# ms5839_with_trub.net
KiCad netlist of a schematic drawn in EAGLE
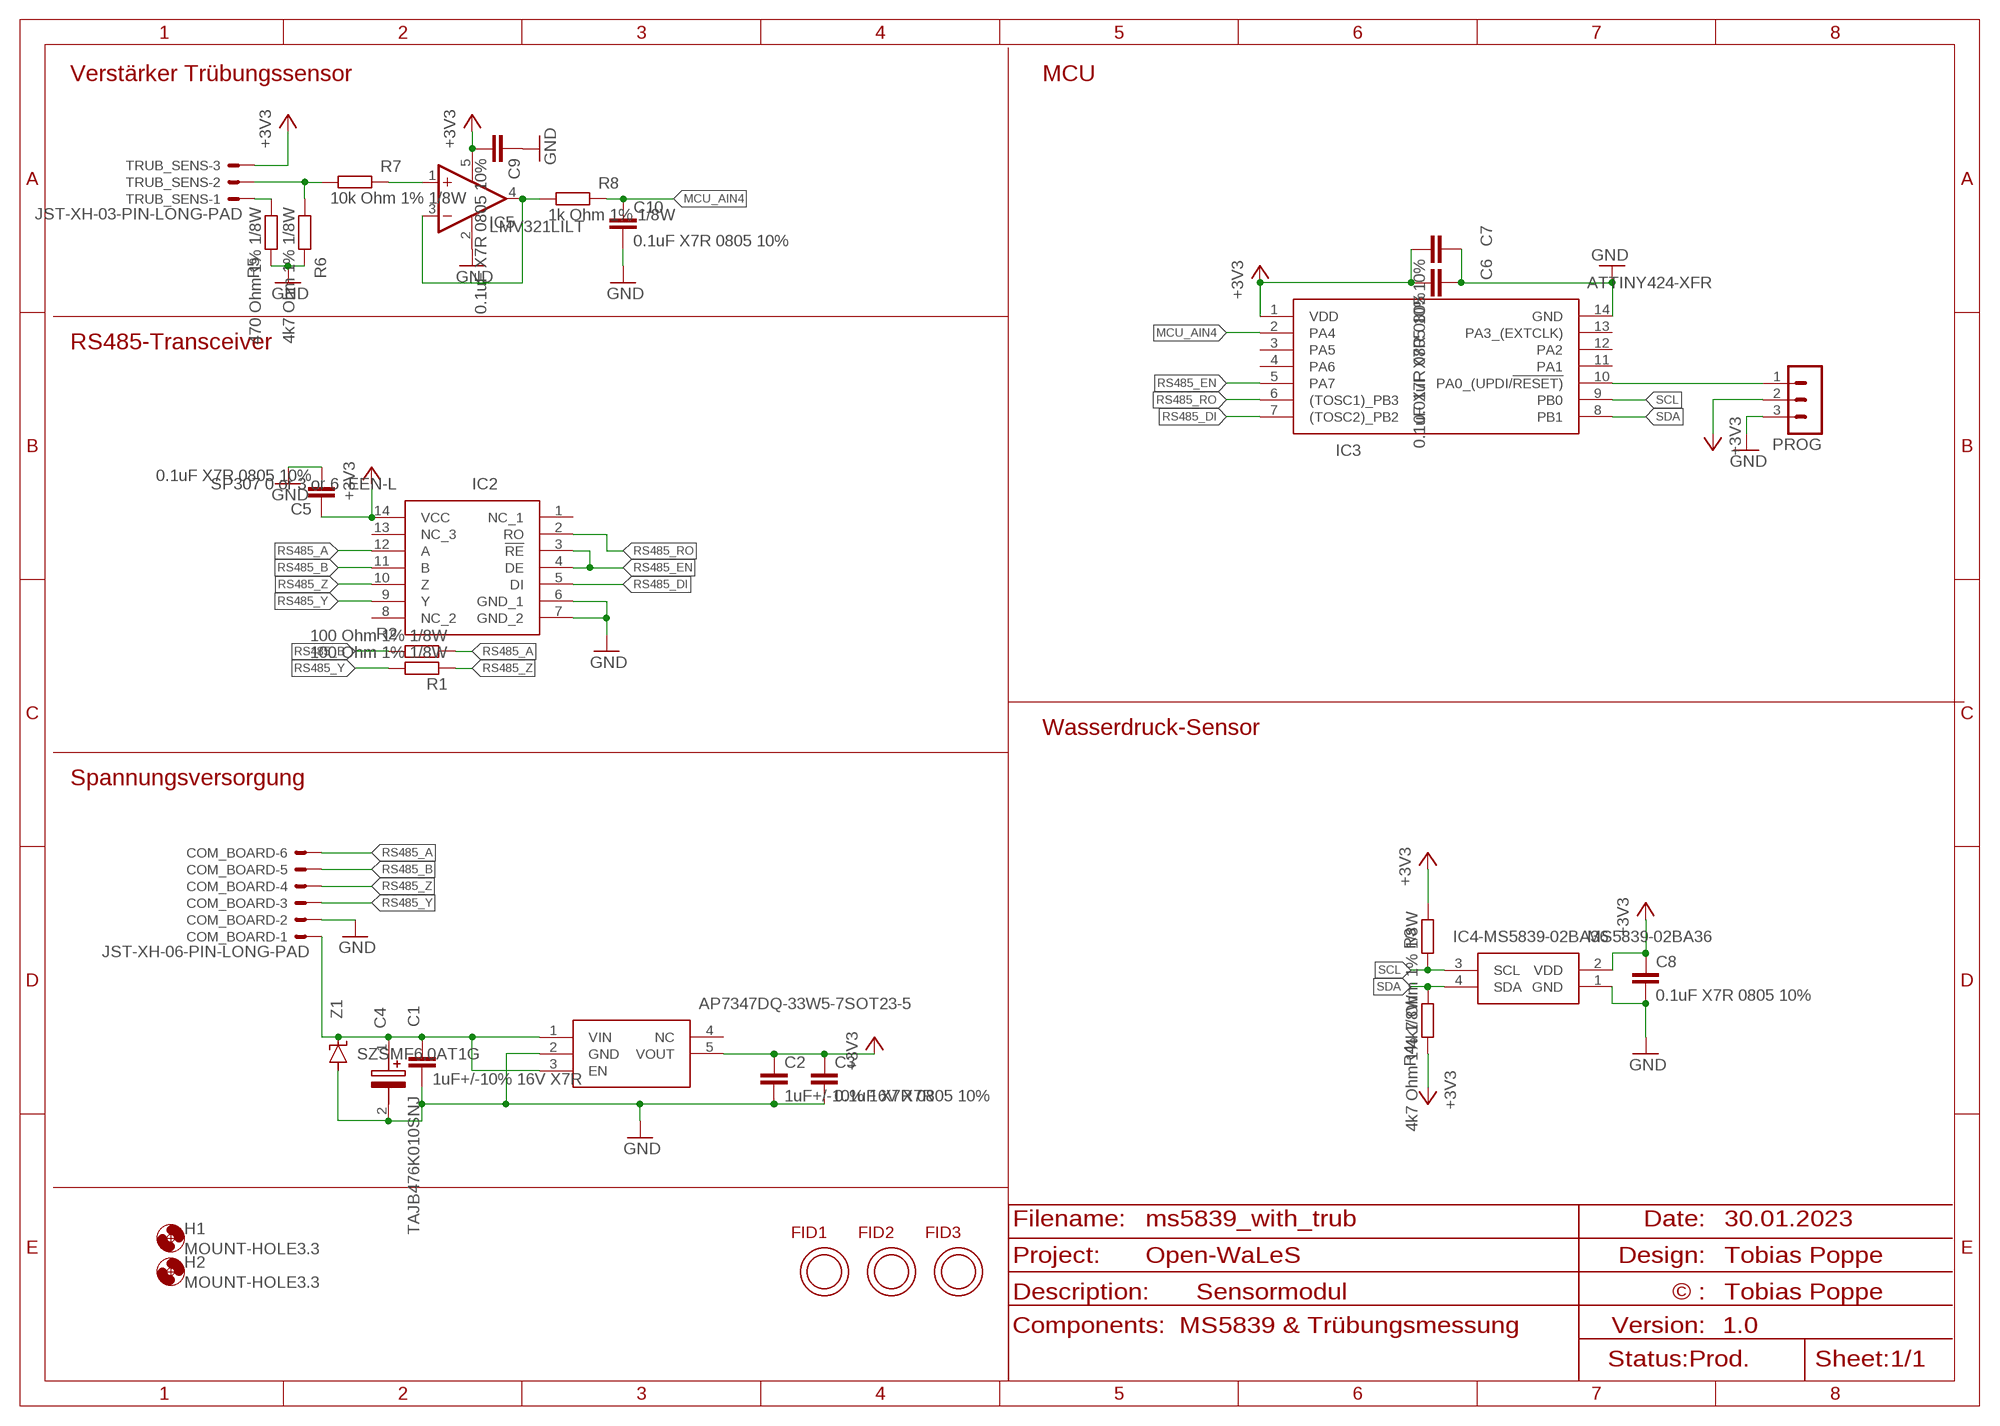
[diagram p0: schematic, sheet 1]

(export (version "E")
  (design (tool "Eeschema 10.0.6"))
  (components
    (comp (ref "C1")
      (value "1uF+/-10% 16V X7R")
      (footprint "eagle-import:C0805")
      (libsource (lib "eagle-import") (part "C-EUC0805"))
    )
    (comp (ref "C2")
      (value "1uF+/-10% 16V X7R")
      (footprint "eagle-import:C0805")
      (libsource (lib "eagle-import") (part "C-EUC0805"))
    )
    (comp (ref "C3")
      (value "0.1uF X7R 0805 10%")
      (footprint "eagle-import:C0805")
      (libsource (lib "eagle-import") (part "C-EUC0805"))
    )
    (comp (ref "C4")
      (value "TAJB476K010SNJ")
      (footprint "eagle-import:CAPPM3528X210N")
      (fields (field (name "MOUSER_PART_NUMBER") "581-TAJB476K010SNJ"))
      (libsource (lib "eagle-import") (part "TAJB476K010SNJ"))
    )
    (comp (ref "C5")
      (value "0.1uF X7R 0805 10%")
      (footprint "eagle-import:C0805")
      (libsource (lib "eagle-import") (part "C-EUC0805"))
    )
    (comp (ref "C6")
      (value "0.1uF X7R 0805 10%")
      (footprint "eagle-import:C0805")
      (libsource (lib "eagle-import") (part "C-EUC0805"))
    )
    (comp (ref "C7")
      (value "0.01uF X7R 0805 10%")
      (footprint "eagle-import:C0805")
      (libsource (lib "eagle-import") (part "C-EUC0805"))
    )
    (comp (ref "C8")
      (value "0.1uF X7R 0805 10%")
      (footprint "eagle-import:C0805")
      (libsource (lib "eagle-import") (part "C-EUC0805"))
    )
    (comp (ref "C9")
      (value "0.1uF X7R 0805 10%")
      (footprint "eagle-import:C0805")
      (libsource (lib "eagle-import") (part "C-EUC0805"))
    )
    (comp (ref "C10")
      (value "0.1uF X7R 0805 10%")
      (footprint "eagle-import:C0805")
      (libsource (lib "eagle-import") (part "C-EUC0805"))
    )
    (comp (ref "COM_BOARD")
      (value "JST-XH-06-PIN-LONG-PAD")
      (footprint "eagle-import:JST-XH-06-PACKAGE-LONG-PAD")
      (libsource (lib "eagle-import") (part "JST-XH-06-PIN-LONG-PAD"))
    )
    (comp (ref "FID1")
      (value "OPEN-PNP-FIDUCIAL")
      (footprint "eagle-import:OPEN-PNP-FIDUCIAL")
      (libsource (lib "eagle-import") (part "OPEN-PNP-FIDUCIAL"))
    )
    (comp (ref "FID2")
      (value "OPEN-PNP-FIDUCIAL")
      (footprint "eagle-import:OPEN-PNP-FIDUCIAL")
      (libsource (lib "eagle-import") (part "OPEN-PNP-FIDUCIAL"))
    )
    (comp (ref "FID3")
      (value "OPEN-PNP-FIDUCIAL")
      (footprint "eagle-import:OPEN-PNP-FIDUCIAL")
      (libsource (lib "eagle-import") (part "OPEN-PNP-FIDUCIAL"))
    )
    (comp (ref "H1")
      (value "MOUNT-HOLE3.3")
      (footprint "eagle-import:3,3")
      (libsource (lib "eagle-import") (part "MOUNT-HOLE3.3"))
    )
    (comp (ref "H2")
      (value "MOUNT-HOLE3.3")
      (footprint "eagle-import:3,3")
      (libsource (lib "eagle-import") (part "MOUNT-HOLE3.3"))
    )
    (comp (ref "IC1")
      (value "AP7347DQ-33W5-7SOT23-5")
      (footprint "eagle-import:SOT95P240X110-5N")
      (libsource (lib "eagle-import") (part "AP7347DQ-33W5-7SOT23-5"))
    )
    (comp (ref "IC2")
      (value "SP307 0 or 3 or 6 EEN-L")
      (footprint "eagle-import:SOIC127P600X175-14N")
      (fields
        (field (name "MANUFACTURER_PART_NUMBER") "SP3076EEN-L")
        (field (name "MOUSER_PART_NUMBER") "701-SP3076EEN-L")
      )
      (libsource (lib "eagle-import") (part "SP3076EEN-L"))
    )
    (comp (ref "IC3")
      (value "ATTINY424-XFR")
      (footprint "eagle-import:SOP65P640X120-14N")
      (fields (field (name "MOUSER_PART_NUMBER") "579-ATTINY424-XFR"))
      (libsource (lib "eagle-import") (part "ATTINY424-XFR"))
    )
    (comp (ref "IC4-MS5839-02BA36")
      (value "MS5839-02BA36")
      (footprint "eagle-import:MS583902BA36")
      (fields (field (name "MOUSER_PART_NUMBER") "824-MS5839-02BA36"))
      (libsource (lib "eagle-import") (part "MS5839-02BA36"))
    )
    (comp (ref "IC5")
      (value "LMV321LILT")
      (footprint "eagle-import:SOT23-5")
      (libsource (lib "eagle-import") (part "LMV321?M5X"))
    )
    (comp (ref "PROG")
      (value "MA03-1")
      (footprint "eagle-import:MA03-1")
      (libsource (lib "eagle-import") (part "MA03-1"))
    )
    (comp (ref "R1")
      (value "100 Ohm 1% 1/8W")
      (footprint "eagle-import:R0805")
      (libsource (lib "eagle-import") (part "R-EU_R0805"))
    )
    (comp (ref "R2")
      (value "100 Ohm 1% 1/8W")
      (footprint "eagle-import:R0805")
      (libsource (lib "eagle-import") (part "R-EU_R0805"))
    )
    (comp (ref "R3")
      (value "4k7 Ohm 1% 1/8W")
      (footprint "eagle-import:R0805")
      (libsource (lib "eagle-import") (part "R-EU_R0805"))
    )
    (comp (ref "R4")
      (value "4k7 Ohm 1% 1/8W")
      (footprint "eagle-import:R0805")
      (libsource (lib "eagle-import") (part "R-EU_R0805"))
    )
    (comp (ref "R5")
      (value "470 Ohm 1% 1/8W")
      (footprint "eagle-import:R0805")
      (libsource (lib "eagle-import") (part "R-EU_R0805"))
    )
    (comp (ref "R6")
      (value "4k7 Ohm 1% 1/8W")
      (footprint "eagle-import:R0805")
      (libsource (lib "eagle-import") (part "R-EU_R0805"))
    )
    (comp (ref "R7")
      (value "10k Ohm 1% 1/8W")
      (footprint "eagle-import:R0805")
      (libsource (lib "eagle-import") (part "R-EU_R0805"))
    )
    (comp (ref "R8")
      (value "1k Ohm 1% 1/8W")
      (footprint "eagle-import:R0805")
      (libsource (lib "eagle-import") (part "R-EU_R0805"))
    )
    (comp (ref "TRUB_SENS")
      (value "JST-XH-03-PIN-LONG-PAD")
      (footprint "eagle-import:JST-XH-03-PACKAGE-LONG-PAD")
      (libsource (lib "eagle-import") (part "JST-XH-03-PIN-LONG-PAD"))
    )
    (comp (ref "Z1")
      (value "SZSMF6.0AT1G")
      (footprint "eagle-import:SOD123")
      (libsource (lib "eagle-import") (part "SZSMF_XX"))
    )
  )
  (nets
    (net (code "1") (name "+3V3") (class "Default")
      (node (ref "C2") (pin "1") (pinfunction "1_1") (pintype "passive"))
      (node (ref "C3") (pin "1") (pinfunction "1_1") (pintype "passive"))
      (node (ref "C5") (pin "1") (pinfunction "1_1") (pintype "passive"))
      (node (ref "C6") (pin "2") (pinfunction "2_2") (pintype "passive"))
      (node (ref "C7") (pin "2") (pinfunction "2_2") (pintype "passive"))
      (node (ref "C8") (pin "1") (pinfunction "1_1") (pintype "passive"))
      (node (ref "C9") (pin "2") (pinfunction "2_2") (pintype "passive"))
      (node (ref "IC1") (pin "5") (pinfunction "VOUT_5") (pintype "bidirectional"))
      (node (ref "IC2") (pin "14") (pinfunction "VCC_14") (pintype "bidirectional"))
      (node (ref "IC3") (pin "1") (pinfunction "VDD_1") (pintype "bidirectional"))
      (node (ref "IC4-MS5839-02BA36") (pin "2") (pinfunction "VDD_2") (pintype "bidirectional"))
      (node (ref "IC5") (pin "5") (pinfunction "V+_5") (pintype "power_in"))
      (node (ref "PROG") (pin "2") (pinfunction "2_2") (pintype "passive"))
      (node (ref "R3") (pin "1") (pinfunction "1_1") (pintype "passive"))
      (node (ref "R4") (pin "2") (pinfunction "2_2") (pintype "passive"))
      (node (ref "TRUB_SENS") (pin "3") (pinfunction "S_3") (pintype "passive"))
    )
    (net (code "2") (name "GND") (class "Default")
      (node (ref "C1") (pin "2") (pinfunction "2_2") (pintype "passive"))
      (node (ref "C10") (pin "2") (pinfunction "2_2") (pintype "passive"))
      (node (ref "C2") (pin "2") (pinfunction "2_2") (pintype "passive"))
      (node (ref "C3") (pin "2") (pinfunction "2_2") (pintype "passive"))
      (node (ref "C4") (pin "2") (pinfunction "-_2") (pintype "bidirectional"))
      (node (ref "C5") (pin "2") (pinfunction "2_2") (pintype "passive"))
      (node (ref "C6") (pin "1") (pinfunction "1_1") (pintype "passive"))
      (node (ref "C7") (pin "1") (pinfunction "1_1") (pintype "passive"))
      (node (ref "C8") (pin "2") (pinfunction "2_2") (pintype "passive"))
      (node (ref "C9") (pin "1") (pinfunction "1_1") (pintype "passive"))
      (node (ref "COM_BOARD") (pin "2") (pinfunction "S_2") (pintype "passive"))
      (node (ref "IC1") (pin "2") (pinfunction "GND_2") (pintype "bidirectional"))
      (node (ref "IC2") (pin "6") (pinfunction "GND_1_6") (pintype "bidirectional"))
      (node (ref "IC2") (pin "7") (pinfunction "GND_2_7") (pintype "bidirectional"))
      (node (ref "IC3") (pin "14") (pinfunction "GND_14") (pintype "bidirectional"))
      (node (ref "IC4-MS5839-02BA36") (pin "1") (pinfunction "GND_1") (pintype "bidirectional"))
      (node (ref "IC5") (pin "2") (pinfunction "V-_2") (pintype "power_in"))
      (node (ref "PROG") (pin "3") (pinfunction "3_3") (pintype "passive"))
      (node (ref "R5") (pin "2") (pinfunction "2_2") (pintype "passive"))
      (node (ref "R6") (pin "2") (pinfunction "2_2") (pintype "passive"))
      (node (ref "Z1") (pin "A") (pinfunction "A_A") (pintype "passive"))
    )
    (net (code "3") (name "MCU_AIN4") (class "Default")
      (node (ref "C10") (pin "1") (pinfunction "1_1") (pintype "passive"))
      (node (ref "IC3") (pin "2") (pinfunction "PA4_2") (pintype "bidirectional"))
      (node (ref "R8") (pin "2") (pinfunction "2_2") (pintype "passive"))
    )
    (net (code "4") (name "Net-(C4-+)") (class "Default")
      (node (ref "C1") (pin "1") (pinfunction "1_1") (pintype "passive"))
      (node (ref "C4") (pin "1") (pinfunction "+_1") (pintype "bidirectional"))
      (node (ref "COM_BOARD") (pin "1") (pinfunction "S_1") (pintype "passive"))
      (node (ref "IC1") (pin "1") (pinfunction "VIN_1") (pintype "bidirectional"))
      (node (ref "IC1") (pin "3") (pinfunction "EN_3") (pintype "bidirectional"))
      (node (ref "Z1") (pin "C") (pinfunction "C_C") (pintype "passive"))
    )
    (net (code "5") (name "Net-(IC3-PA0_(UPDI{slash}~{RESET}))") (class "Default")
      (node (ref "IC3") (pin "10") (pinfunction "PA0_(UPDI/~{RESET})_10") (pintype "bidirectional"))
      (node (ref "PROG") (pin "1") (pinfunction "1_1") (pintype "passive"))
    )
    (net (code "6") (name "Net-(IC5-+IN)") (class "Default")
      (node (ref "IC5") (pin "1") (pinfunction "+IN_1") (pintype "input"))
      (node (ref "R7") (pin "2") (pinfunction "2_2") (pintype "passive"))
    )
    (net (code "7") (name "Net-(IC5--IN)") (class "Default")
      (node (ref "IC5") (pin "3") (pinfunction "-IN_3") (pintype "input"))
      (node (ref "IC5") (pin "4") (pinfunction "OUT_4") (pintype "output"))
      (node (ref "R8") (pin "1") (pinfunction "1_1") (pintype "passive"))
    )
    (net (code "8") (name "Net-(TRUB_SENSA-S)") (class "Default")
      (node (ref "R5") (pin "1") (pinfunction "1_1") (pintype "passive"))
      (node (ref "TRUB_SENS") (pin "1") (pinfunction "S_1") (pintype "passive"))
    )
    (net (code "9") (name "Net-(TRUB_SENSB-S)") (class "Default")
      (node (ref "R6") (pin "1") (pinfunction "1_1") (pintype "passive"))
      (node (ref "R7") (pin "1") (pinfunction "1_1") (pintype "passive"))
      (node (ref "TRUB_SENS") (pin "2") (pinfunction "S_2") (pintype "passive"))
    )
    (net (code "10") (name "RS485_A") (class "Default")
      (node (ref "COM_BOARD") (pin "6") (pinfunction "S_6") (pintype "passive"))
      (node (ref "IC2") (pin "12") (pinfunction "A_12") (pintype "bidirectional"))
      (node (ref "R2") (pin "1") (pinfunction "1_1") (pintype "passive"))
    )
    (net (code "11") (name "RS485_B") (class "Default")
      (node (ref "COM_BOARD") (pin "5") (pinfunction "S_5") (pintype "passive"))
      (node (ref "IC2") (pin "11") (pinfunction "B_11") (pintype "bidirectional"))
      (node (ref "R2") (pin "2") (pinfunction "2_2") (pintype "passive"))
    )
    (net (code "12") (name "RS485_DI") (class "Default")
      (node (ref "IC2") (pin "5") (pinfunction "DI_5") (pintype "bidirectional"))
      (node (ref "IC3") (pin "7") (pinfunction "(TOSC2)_PB2_7") (pintype "bidirectional"))
    )
    (net (code "13") (name "RS485_EN") (class "Default")
      (node (ref "IC2") (pin "3") (pinfunction "~{RE}_3") (pintype "bidirectional"))
      (node (ref "IC2") (pin "4") (pinfunction "DE_4") (pintype "bidirectional"))
      (node (ref "IC3") (pin "5") (pinfunction "PA7_5") (pintype "bidirectional"))
    )
    (net (code "14") (name "RS485_RO") (class "Default")
      (node (ref "IC2") (pin "2") (pinfunction "RO_2") (pintype "bidirectional"))
      (node (ref "IC3") (pin "6") (pinfunction "(TOSC1)_PB3_6") (pintype "bidirectional"))
    )
    (net (code "15") (name "RS485_Y") (class "Default")
      (node (ref "COM_BOARD") (pin "3") (pinfunction "S_3") (pintype "passive"))
      (node (ref "IC2") (pin "9") (pinfunction "Y_9") (pintype "bidirectional"))
      (node (ref "R1") (pin "2") (pinfunction "2_2") (pintype "passive"))
    )
    (net (code "16") (name "RS485_Z") (class "Default")
      (node (ref "COM_BOARD") (pin "4") (pinfunction "S_4") (pintype "passive"))
      (node (ref "IC2") (pin "10") (pinfunction "Z_10") (pintype "bidirectional"))
      (node (ref "R1") (pin "1") (pinfunction "1_1") (pintype "passive"))
    )
    (net (code "17") (name "SCL") (class "Default")
      (node (ref "IC3") (pin "9") (pinfunction "PB0_9") (pintype "bidirectional"))
      (node (ref "IC4-MS5839-02BA36") (pin "3") (pinfunction "SCL_3") (pintype "bidirectional"))
      (node (ref "R3") (pin "2") (pinfunction "2_2") (pintype "passive"))
    )
    (net (code "18") (name "SDA") (class "Default")
      (node (ref "IC3") (pin "8") (pinfunction "PB1_8") (pintype "bidirectional"))
      (node (ref "IC4-MS5839-02BA36") (pin "4") (pinfunction "SDA_4") (pintype "bidirectional"))
      (node (ref "R4") (pin "1") (pinfunction "1_1") (pintype "passive"))
    )
    (net (code "19") (name "unconnected-(IC1-NC-Pad4)") (class "Default")
      (node (ref "IC1") (pin "4") (pinfunction "NC_4") (pintype "no_connect"))
    )
    (net (code "20") (name "unconnected-(IC2-NC_1-Pad1)") (class "Default")
      (node (ref "IC2") (pin "1") (pinfunction "NC_1_1") (pintype "bidirectional"))
    )
    (net (code "21") (name "unconnected-(IC2-NC_2-Pad8)") (class "Default")
      (node (ref "IC2") (pin "8") (pinfunction "NC_2_8") (pintype "bidirectional"))
    )
    (net (code "22") (name "unconnected-(IC2-NC_3-Pad13)") (class "Default")
      (node (ref "IC2") (pin "13") (pinfunction "NC_3_13") (pintype "bidirectional"))
    )
    (net (code "23") (name "unconnected-(IC3-PA1-Pad11)") (class "Default")
      (node (ref "IC3") (pin "11") (pinfunction "PA1_11") (pintype "bidirectional"))
    )
    (net (code "24") (name "unconnected-(IC3-PA2-Pad12)") (class "Default")
      (node (ref "IC3") (pin "12") (pinfunction "PA2_12") (pintype "bidirectional"))
    )
    (net (code "25") (name "unconnected-(IC3-PA3_(EXTCLK)-Pad13)") (class "Default")
      (node (ref "IC3") (pin "13") (pinfunction "PA3_(EXTCLK)_13") (pintype "bidirectional"))
    )
    (net (code "26") (name "unconnected-(IC3-PA5-Pad3)") (class "Default")
      (node (ref "IC3") (pin "3") (pinfunction "PA5_3") (pintype "bidirectional"))
    )
    (net (code "27") (name "unconnected-(IC3-PA6-Pad4)") (class "Default")
      (node (ref "IC3") (pin "4") (pinfunction "PA6_4") (pintype "bidirectional"))
    )
  )
)
